# Power.net
KiCad netlist of a schematic drawn in Altium Designer
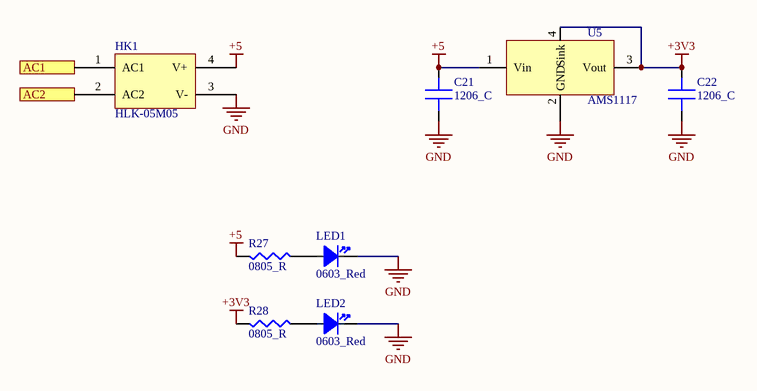
[diagram p0: Power.SchDoc]

(export (version "E")
  (design (tool "Eeschema 10.0.6"))
  (components
    (comp (ref "C21")
      (value "1206_C")
      (footprint "1206")
      (description "1206 Capacitor")
      (libsource (lib "TimerSMD_Components") (part "1206 Capacitor"))
    )
    (comp (ref "C22")
      (value "1206_C")
      (footprint "1206")
      (description "1206 Capacitor")
      (libsource (lib "TimerSMD_Components") (part "1206 Capacitor"))
    )
    (comp (ref "HK1")
      (value "HLK-05M05")
      (footprint "HLK-05M05")
      (libsource (lib "EV_Symbols") (part "HLK-05M05"))
    )
    (comp (ref "LED1")
      (value "0603_Red")
      (footprint "0603_LED")
      (libsource (lib "TimerSMD_Components") (part "0603LED"))
    )
    (comp (ref "LED2")
      (value "0603_Red")
      (footprint "0603_LED")
      (libsource (lib "TimerSMD_Components") (part "0603LED"))
    )
    (comp (ref "R27")
      (value "0805_R")
      (footprint "R0805")
      (libsource (lib "TimerSMD_Components") (part "0805 Resistor"))
    )
    (comp (ref "R28")
      (value "0805_R")
      (footprint "R0805")
      (libsource (lib "TimerSMD_Components") (part "0805 Resistor"))
    )
    (comp (ref "U5")
      (value "AMS1117")
      (footprint "SOT-223")
      (libsource (lib "TimerSMD_Components") (part "AMS1117 - 3V3"))
    )
  )
  (nets
    (net (code "1") (name "+3V3") (class "Default")
      (node (ref "C22") (pin "2") (pinfunction "2_2") (pintype "passive"))
      (node (ref "R28") (pin "1") (pinfunction "1_1") (pintype "passive"))
      (node (ref "U5") (pin "3") (pinfunction "Vout_3") (pintype "passive"))
      (node (ref "U5") (pin "4") (pinfunction "Sink_4") (pintype "passive"))
    )
    (net (code "2") (name "+5") (class "Default")
      (node (ref "C21") (pin "2") (pinfunction "2_2") (pintype "passive"))
      (node (ref "HK1") (pin "4") (pinfunction "V+_4") (pintype "passive"))
      (node (ref "R27") (pin "1") (pinfunction "1_1") (pintype "passive"))
      (node (ref "U5") (pin "1") (pinfunction "Vin_1") (pintype "passive"))
    )
    (net (code "3") (name "/AC1") (class "Default")
      (node (ref "HK1") (pin "1") (pinfunction "AC1_1") (pintype "passive"))
    )
    (net (code "4") (name "/AC2") (class "Default")
      (node (ref "HK1") (pin "2") (pinfunction "AC2_2") (pintype "passive"))
    )
    (net (code "5") (name "GND") (class "Default")
      (node (ref "C21") (pin "1") (pinfunction "1_1") (pintype "passive"))
      (node (ref "C22") (pin "1") (pinfunction "1_1") (pintype "passive"))
      (node (ref "HK1") (pin "3") (pinfunction "V-_3") (pintype "passive"))
      (node (ref "LED1") (pin "2") (pinfunction "Cathode_2") (pintype "passive"))
      (node (ref "LED2") (pin "2") (pinfunction "Cathode_2") (pintype "passive"))
      (node (ref "U5") (pin "2") (pinfunction "GND_2") (pintype "passive"))
    )
    (net (code "6") (name "Net-(LED1-Anode)") (class "Default")
      (node (ref "LED1") (pin "1") (pinfunction "Anode_1") (pintype "passive"))
      (node (ref "R27") (pin "2") (pinfunction "2_2") (pintype "passive"))
    )
    (net (code "7") (name "Net-(LED2-Anode)") (class "Default")
      (node (ref "LED2") (pin "1") (pinfunction "Anode_1") (pintype "passive"))
      (node (ref "R28") (pin "2") (pinfunction "2_2") (pintype "passive"))
    )
  )
)
